# vizics.net
KiCad netlist of a schematic drawn in Altium Designer
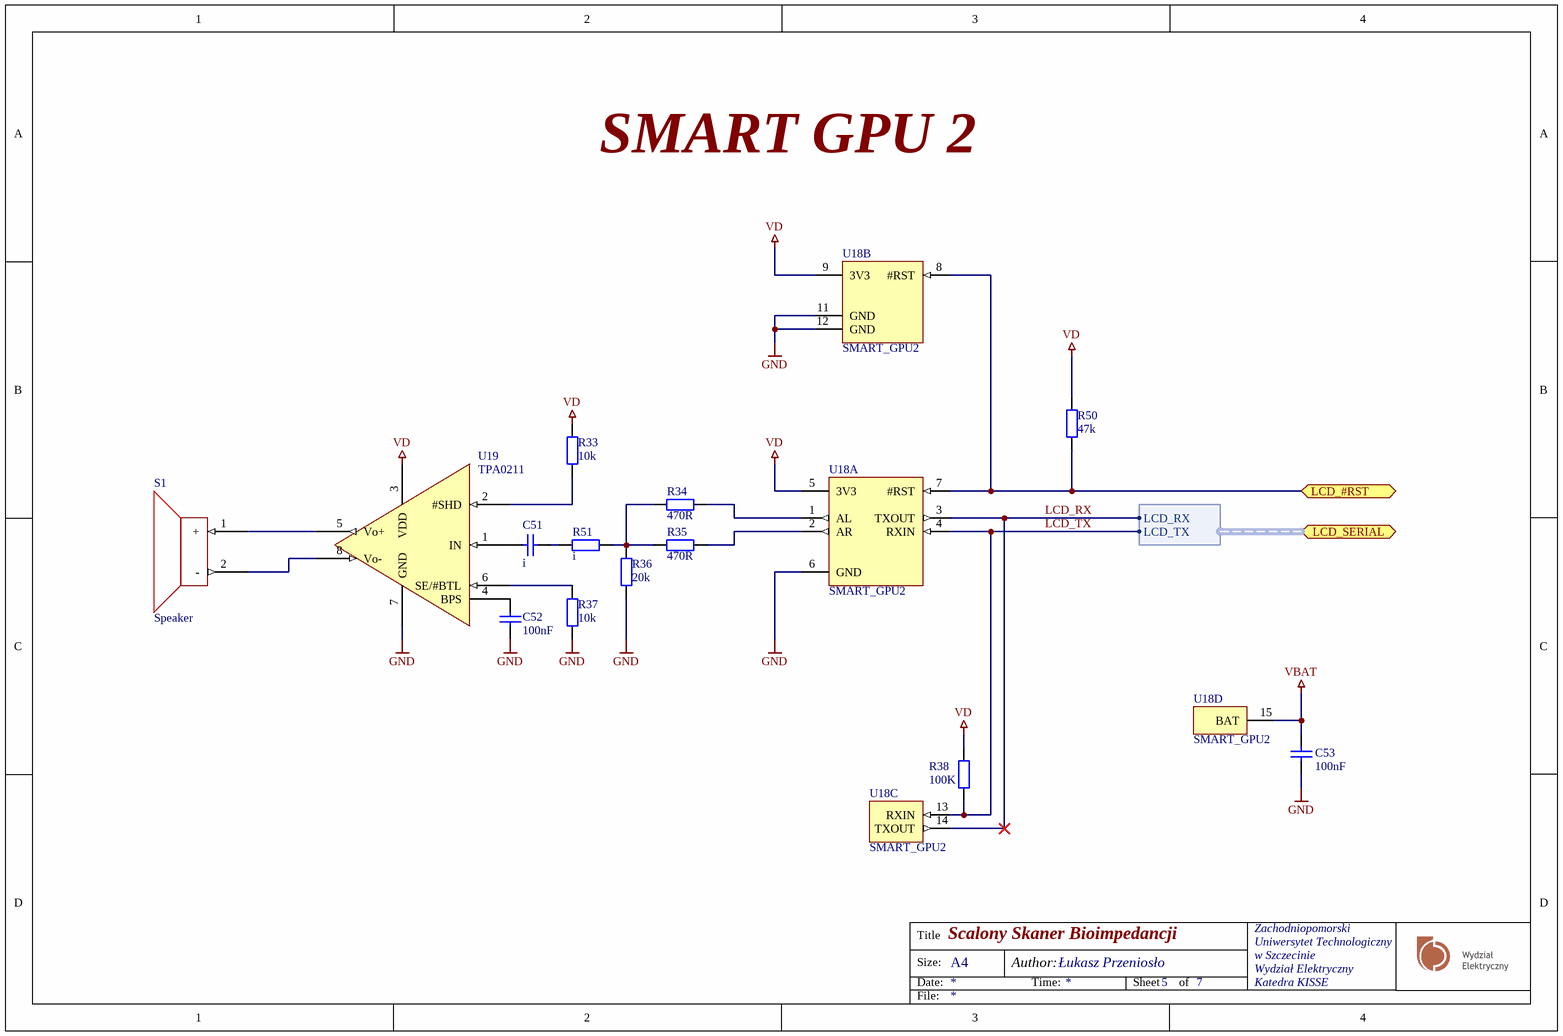
[diagram p0: vizics.SchDoc]

(export (version "E")
  (design (tool "Eeschema 10.0.6"))
  (components
    (comp (ref "C51")
      (value "i")
      (footprint "CAPC1608N")
      (description "Capacitor")
      (libsource (lib "Discrete") (part "Capacitor"))
    )
    (comp (ref "C52")
      (value "100nF")
      (footprint "CAPC1608N")
      (description "Capacitor")
      (libsource (lib "Discrete") (part "Capacitor"))
    )
    (comp (ref "C53")
      (value "100nF")
      (footprint "CAPC1608N")
      (description "Capacitor")
      (libsource (lib "Discrete") (part "Capacitor"))
    )
    (comp (ref "R33")
      (value "10k")
      (footprint "RESC1608N")
      (description "Resistor")
      (fields (field (name "TOLERANCE") "5%") (field (name "POWER") "0W"))
      (libsource (lib "Discrete") (part "Resistor"))
    )
    (comp (ref "R34")
      (value "470R")
      (footprint "RESC1608N")
      (description "Resistor")
      (fields (field (name "TOLERANCE") "5%") (field (name "POWER") "0W"))
      (libsource (lib "") (part "Resistor_3"))
    )
    (comp (ref "R35")
      (value "470R")
      (footprint "RESC1608N")
      (description "Resistor")
      (fields (field (name "TOLERANCE") "5%") (field (name "POWER") "0W"))
      (libsource (lib "") (part "Resistor_3"))
    )
    (comp (ref "R36")
      (value "20k")
      (footprint "RESC1608N")
      (description "Resistor")
      (fields (field (name "TOLERANCE") "5%") (field (name "POWER") "0W"))
      (libsource (lib "Discrete") (part "Resistor"))
    )
    (comp (ref "R37")
      (value "10k")
      (footprint "RESC1608N")
      (description "Resistor")
      (fields (field (name "TOLERANCE") "5%") (field (name "POWER") "0W"))
      (libsource (lib "") (part "Resistor_1"))
    )
    (comp (ref "R38")
      (value "100K")
      (footprint "RESC1608N")
      (description "Resistor")
      (fields (field (name "POWER") "0W") (field (name "TOLERANCE") "5%"))
      (libsource (lib "") (part "Resistor_2"))
    )
    (comp (ref "R50")
      (value "47k")
      (footprint "RESC1608N")
      (description "Resistor")
      (fields (field (name "TOLERANCE") "5%") (field (name "POWER") "0W"))
      (libsource (lib "Discrete") (part "Resistor"))
    )
    (comp (ref "R51")
      (value "i")
      (footprint "RESC1608N")
      (description "Resistor")
      (fields (field (name "TOLERANCE") "5%") (field (name "POWER") "0W"))
      (libsource (lib "") (part "Resistor_3"))
    )
    (comp (ref "S1")
      (value "Speaker")
      (footprint "MX-02227-2021")
      (libsource (lib "Speaker_symbol") (part "Speaker"))
    )
    (comp (ref "U18")
      (value "SMART_GPU2")
      (footprint "LCD_HEADERS")
      (libsource (lib "") (part "SMART_GPU2_2"))
    )
    (comp (ref "U19")
      (value "TPA0211")
      (footprint "SOIC127P600-8AL")
      (libsource (lib "TPA0211") (part "TPA0211"))
    )
  )
  (nets
    (net (code "2") (name "/LCD_#RST") (class "Default")
      (node (ref "R50") (pin "2") (pinfunction "2_2") (pintype "passive"))
      (node (ref "U18") (pin "7") (pinfunction "#RST_7") (pintype "input"))
      (node (ref "U18") (pin "8") (pinfunction "#RST_8") (pintype "input"))
    )
    (net (code "3") (name "/LCD_RX") (class "Default")
      (node (ref "U18") (pin "14") (pinfunction "TXOUT_14") (pintype "output"))
      (node (ref "U18") (pin "3") (pinfunction "TXOUT_3") (pintype "output"))
    )
    (net (code "4") (name "/LCD_TX") (class "Default")
      (node (ref "R38") (pin "1") (pinfunction "1_1") (pintype "passive"))
      (node (ref "U18") (pin "13") (pinfunction "RXIN_13") (pintype "input"))
      (node (ref "U18") (pin "4") (pinfunction "RXIN_4") (pintype "input"))
    )
    (net (code "6") (name "GND") (class "Default")
      (node (ref "C52") (pin "2") (pinfunction "2_2") (pintype "passive"))
      (node (ref "C53") (pin "1") (pinfunction "1_1") (pintype "passive"))
      (node (ref "R36") (pin "2") (pinfunction "2_2") (pintype "passive"))
      (node (ref "R37") (pin "1") (pinfunction "1_1") (pintype "passive"))
      (node (ref "U18") (pin "11") (pinfunction "GND_11") (pintype "power_in"))
      (node (ref "U18") (pin "12") (pinfunction "GND_12") (pintype "power_in"))
      (node (ref "U18") (pin "6") (pinfunction "GND_6") (pintype "power_in"))
      (node (ref "U19") (pin "7") (pinfunction "GND_7") (pintype "power_in"))
    )
    (net (code "7") (name "Net-(C51-Pad1)") (class "Default")
      (node (ref "C51") (pin "1") (pinfunction "1_1") (pintype "passive"))
      (node (ref "R51") (pin "2") (pinfunction "2_2") (pintype "passive"))
    )
    (net (code "8") (name "Net-(R34-Pad2)") (class "Default")
      (node (ref "R34") (pin "2") (pinfunction "2_2") (pintype "passive"))
      (node (ref "R35") (pin "2") (pinfunction "2_2") (pintype "passive"))
      (node (ref "R36") (pin "1") (pinfunction "1_1") (pintype "passive"))
      (node (ref "R51") (pin "1") (pinfunction "1_1") (pintype "passive"))
    )
    (net (code "9") (name "Net-(S1-+)") (class "Default")
      (node (ref "S1") (pin "1") (pinfunction "+_1") (pintype "input"))
      (node (ref "U19") (pin "5") (pinfunction "Vo+_5") (pintype "output"))
    )
    (net (code "10") (name "Net-(S1--)") (class "Default")
      (node (ref "S1") (pin "2") (pinfunction "-_2") (pintype "output"))
      (node (ref "U19") (pin "8") (pinfunction "Vo-_8") (pintype "input"))
    )
    (net (code "11") (name "Net-(U18A-AL)") (class "Default")
      (node (ref "R34") (pin "1") (pinfunction "1_1") (pintype "passive"))
      (node (ref "U18") (pin "1") (pinfunction "AL_1") (pintype "output"))
    )
    (net (code "12") (name "Net-(U18A-AR)") (class "Default")
      (node (ref "R35") (pin "1") (pinfunction "1_1") (pintype "passive"))
      (node (ref "U18") (pin "2") (pinfunction "AR_2") (pintype "output"))
    )
    (net (code "13") (name "Net-(U19-#SHD)") (class "Default")
      (node (ref "R33") (pin "2") (pinfunction "2_2") (pintype "passive"))
      (node (ref "U19") (pin "2") (pinfunction "#SHD_2") (pintype "input"))
    )
    (net (code "14") (name "Net-(U19-BPS)") (class "Default")
      (node (ref "C52") (pin "1") (pinfunction "1_1") (pintype "passive"))
      (node (ref "U19") (pin "4") (pinfunction "BPS_4") (pintype "passive"))
    )
    (net (code "15") (name "Net-(U19-IN)") (class "Default")
      (node (ref "C51") (pin "2") (pinfunction "2_2") (pintype "passive"))
      (node (ref "U19") (pin "1") (pinfunction "IN_1") (pintype "input"))
    )
    (net (code "16") (name "Net-(U19-SE{slash}#BTL)") (class "Default")
      (node (ref "R37") (pin "2") (pinfunction "2_2") (pintype "passive"))
      (node (ref "U19") (pin "6") (pinfunction "SE/#BTL_6") (pintype "input"))
    )
    (net (code "17") (name "VBAT") (class "Default")
      (node (ref "C53") (pin "2") (pinfunction "2_2") (pintype "passive"))
      (node (ref "U18") (pin "15") (pinfunction "BAT_15") (pintype "power_in"))
    )
    (net (code "18") (name "VD") (class "Default")
      (node (ref "R33") (pin "1") (pinfunction "1_1") (pintype "passive"))
      (node (ref "R38") (pin "2") (pinfunction "2_2") (pintype "passive"))
      (node (ref "R50") (pin "1") (pinfunction "1_1") (pintype "passive"))
      (node (ref "U18") (pin "5") (pinfunction "3V3_5") (pintype "power_in"))
      (node (ref "U18") (pin "9") (pinfunction "3V3_9") (pintype "power_in"))
      (node (ref "U19") (pin "3") (pinfunction "VDD_3") (pintype "power_in"))
    )
    (net (code "19") (name "unconnected-(U18B-NC-Pad10)") (class "Default")
      (node (ref "U18") (pin "10") (pinfunction "NC_10") (pintype "passive"))
    )
  )
)
